# SCH_glow_cube_v2_2023-04-08_1.net
KiCad netlist of a schematic drawn in EasyEDA
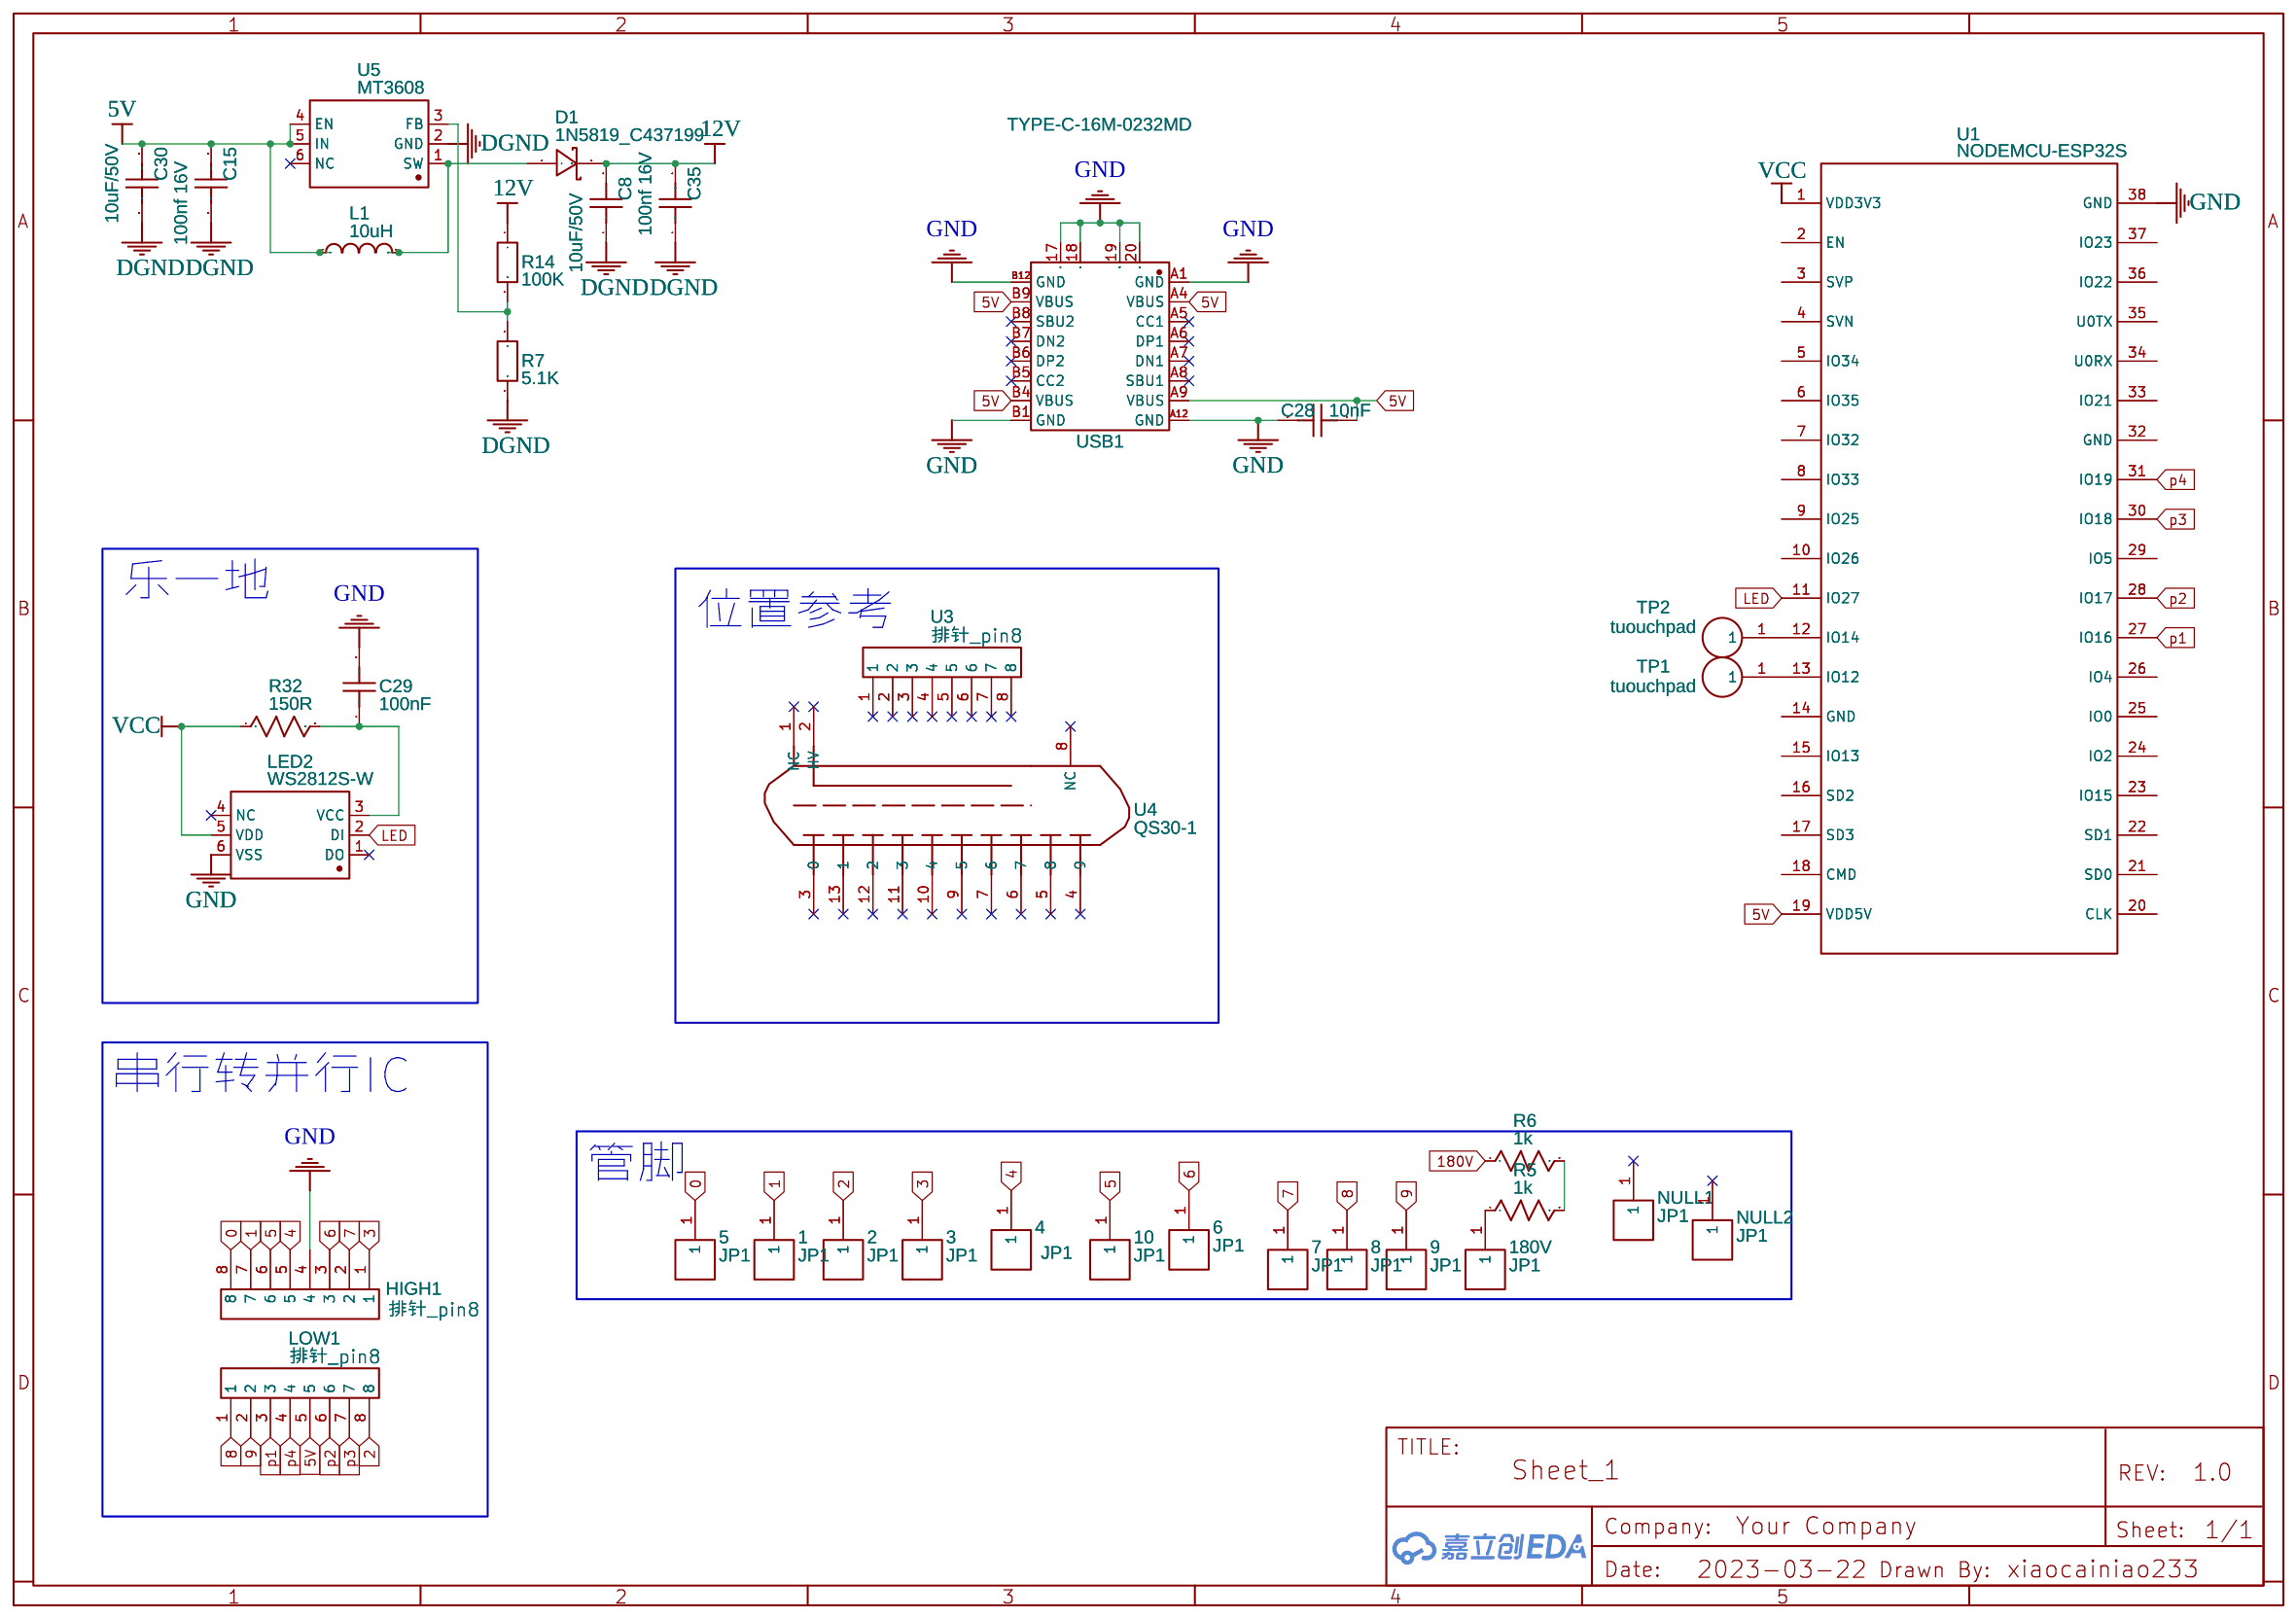
[diagram p0: schematic sheet]

(export (version "E")
  (design (tool "Eeschema 10.0.6"))
  (components
    (comp (ref "1") (value "JP1") (libsource (lib "") (part "JP1")))
    (comp (ref "2") (value "JP1") (libsource (lib "") (part "JP1")))
    (comp (ref "3") (value "JP1") (libsource (lib "") (part "JP1")))
    (comp (ref "4") (value "JP1") (libsource (lib "") (part "JP1")))
    (comp (ref "5") (value "JP1") (libsource (lib "") (part "JP1")))
    (comp (ref "6") (value "JP1") (libsource (lib "") (part "JP1")))
    (comp (ref "7") (value "JP1") (libsource (lib "") (part "JP1")))
    (comp (ref "8") (value "JP1") (libsource (lib "") (part "JP1")))
    (comp (ref "9") (value "JP1") (libsource (lib "") (part "JP1")))
    (comp (ref "10") (value "JP1") (libsource (lib "") (part "JP1")))
    (comp (ref "180V") (value "JP1") (libsource (lib "") (part "JP1_2")))
    (comp (ref "C8") (value "10uF/50V") (libsource (lib "") (part "C_0805_US")))
    (comp (ref "C15") (value "100nf 16V") (libsource (lib "") (part "C_0603_US")))
    (comp (ref "C28") (value "10nF") (libsource (lib "") (part "C_0603_US_1")))
    (comp (ref "C29") (value "100nF") (libsource (lib "") (part "C_0402_US")))
    (comp (ref "C30") (value "10uF/50V") (libsource (lib "") (part "C_0805_US")))
    (comp (ref "C35") (value "100nf 16V") (libsource (lib "") (part "C_0603_US")))
    (comp (ref "D1")
      (value "1N5819_C437199")
      (fields (field (name "BOM_Manufacturer Part") "1N5819") (field (name "BOM_Supplier Part") "C437199"))
      (libsource (lib "") (part "1N5819_C437199"))
    )
    (comp (ref "HIGH1") (value "排针_pin8") (libsource (lib "") (part "排针_pin8")))
    (comp (ref "L1")
      (value "10uH")
      (fields
        (field (name "BOM_Manufacturer Part") "ETQP3M100KVP")
        (field (name "BOM_Supplier Part") "C409619")
      )
      (libsource (lib "") (part "ETQP3M100KVP"))
    )
    (comp (ref "LED2")
      (value "WS2812S-W")
      (fields (field (name "BOM_Manufacturer Part") "WS2812S") (field (name "BOM_Supplier Part") "C114584"))
      (libsource (lib "") (part "WS2812S-W"))
    )
    (comp (ref "LOW1") (value "排针_pin8") (libsource (lib "") (part "排针_pin8_1")))
    (comp (ref "NULL1") (value "JP1") (libsource (lib "") (part "JP1_1")))
    (comp (ref "NULL2") (value "JP1") (libsource (lib "") (part "JP1_1")))
    (comp (ref "R5") (value "1k") (libsource (lib "") (part "R_AXIAL-0.3_US")))
    (comp (ref "R6") (value "1k") (libsource (lib "") (part "R_AXIAL-0.3_US")))
    (comp (ref "R7") (value "5.1K") (libsource (lib "") (part "R_0603_EU")))
    (comp (ref "R14") (value "100K") (libsource (lib "") (part "R_0603_EU")))
    (comp (ref "R32") (value "150R") (libsource (lib "") (part "R_0603_US")))
    (comp (ref "TP1") (value "tuouchpad") (libsource (lib "") (part "tuouchpad")))
    (comp (ref "TP2") (value "tuouchpad") (libsource (lib "") (part "tuouchpad")))
    (comp (ref "U1") (value "NODEMCU-ESP32S") (libsource (lib "") (part "NODEMCU-ESP32S")))
    (comp (ref "U3") (value "排针_pin8") (libsource (lib "") (part "排针_pin8_2")))
    (comp (ref "U4") (value "QS30-1") (libsource (lib "") (part "QS30-1")))
    (comp (ref "U5")
      (value "MT3608")
      (fields (field (name "BOM_Supplier Part") "C84817"))
      (libsource (lib "") (part "MT3608"))
    )
    (comp (ref "USB1")
      (value "TYPE-C-16M-0232MD")
      (fields (field (name "BOM_Supplier Part") "C2798171"))
      (libsource (lib "") (part "TYPE-C-16M-0232MD"))
    )
  )
  (nets
    (net (code "1") (name "0") (class "Default")
      (node (ref "5") (pin "1") (pinfunction "1_1") (pintype "unspecified"))
      (node (ref "HIGH1") (pin "8") (pinfunction "8_8") (pintype "unspecified"))
    )
    (net (code "2") (name "1") (class "Default")
      (node (ref "1") (pin "1") (pinfunction "1_1") (pintype "unspecified"))
      (node (ref "HIGH1") (pin "7") (pinfunction "7_7") (pintype "unspecified"))
    )
    (net (code "3") (name "2") (class "Default")
      (node (ref "2") (pin "1") (pinfunction "1_1") (pintype "unspecified"))
      (node (ref "LOW1") (pin "8") (pinfunction "8_8") (pintype "unspecified"))
    )
    (net (code "4") (name "3") (class "Default")
      (node (ref "3") (pin "1") (pinfunction "1_1") (pintype "unspecified"))
      (node (ref "HIGH1") (pin "1") (pinfunction "1_1") (pintype "unspecified"))
    )
    (net (code "5") (name "4") (class "Default")
      (node (ref "4") (pin "1") (pinfunction "1_1") (pintype "unspecified"))
      (node (ref "HIGH1") (pin "5") (pinfunction "5_5") (pintype "unspecified"))
    )
    (net (code "6") (name "5") (class "Default")
      (node (ref "10") (pin "1") (pinfunction "1_1") (pintype "unspecified"))
      (node (ref "HIGH1") (pin "6") (pinfunction "6_6") (pintype "unspecified"))
    )
    (net (code "7") (name "5V") (class "Default")
      (node (ref "C15") (pin "2") (pinfunction "2_2") (pintype "unspecified"))
      (node (ref "C28") (pin "2") (pinfunction "2_2") (pintype "unspecified"))
      (node (ref "C30") (pin "2") (pinfunction "2_2") (pintype "unspecified"))
      (node (ref "L1") (pin "1") (pinfunction "1_1") (pintype "unspecified"))
      (node (ref "LOW1") (pin "5") (pinfunction "5_5") (pintype "unspecified"))
      (node (ref "U1") (pin "19") (pinfunction "VDD5V_19") (pintype "unspecified"))
      (node (ref "U5") (pin "4") (pinfunction "EN_4") (pintype "unspecified"))
      (node (ref "U5") (pin "5") (pinfunction "IN_5") (pintype "unspecified"))
      (node (ref "USB1") (pin "A4") (pinfunction "VBUS_A4") (pintype "unspecified"))
      (node (ref "USB1") (pin "A9") (pinfunction "VBUS_A9") (pintype "unspecified"))
      (node (ref "USB1") (pin "B4") (pinfunction "VBUS_B4") (pintype "unspecified"))
      (node (ref "USB1") (pin "B9") (pinfunction "VBUS_B9") (pintype "unspecified"))
    )
    (net (code "8") (name "6") (class "Default")
      (node (ref "6") (pin "1") (pinfunction "1_1") (pintype "unspecified"))
      (node (ref "HIGH1") (pin "3") (pinfunction "3_3") (pintype "unspecified"))
    )
    (net (code "9") (name "7") (class "Default")
      (node (ref "7") (pin "1") (pinfunction "1_1") (pintype "unspecified"))
      (node (ref "HIGH1") (pin "2") (pinfunction "2_2") (pintype "unspecified"))
    )
    (net (code "10") (name "8") (class "Default")
      (node (ref "8") (pin "1") (pinfunction "1_1") (pintype "unspecified"))
      (node (ref "LOW1") (pin "1") (pinfunction "1_1") (pintype "unspecified"))
    )
    (net (code "11") (name "9") (class "Default")
      (node (ref "9") (pin "1") (pinfunction "1_1") (pintype "unspecified"))
      (node (ref "LOW1") (pin "2") (pinfunction "2_2") (pintype "unspecified"))
    )
    (net (code "12") (name "12V") (class "Default")
      (node (ref "C35") (pin "2") (pinfunction "2_2") (pintype "unspecified"))
      (node (ref "C8") (pin "2") (pinfunction "2_2") (pintype "unspecified"))
      (node (ref "D1") (pin "1") (pinfunction "C_1") (pintype "unspecified"))
      (node (ref "R14") (pin "1") (pinfunction "1_1") (pintype "unspecified"))
    )
    (net (code "13") (name "180V") (class "Default")
      (node (ref "R6") (pin "1") (pinfunction "1_1") (pintype "unspecified"))
    )
    (net (code "14") (name "DGND") (class "Default")
      (node (ref "C15") (pin "1") (pinfunction "1_1") (pintype "unspecified"))
      (node (ref "C30") (pin "1") (pinfunction "1_1") (pintype "unspecified"))
      (node (ref "C35") (pin "1") (pinfunction "1_1") (pintype "unspecified"))
      (node (ref "C8") (pin "1") (pinfunction "1_1") (pintype "unspecified"))
      (node (ref "R7") (pin "2") (pinfunction "2_2") (pintype "unspecified"))
      (node (ref "U5") (pin "2") (pinfunction "GND_2") (pintype "unspecified"))
    )
    (net (code "15") (name "GND") (class "Default")
      (node (ref "C28") (pin "1") (pinfunction "1_1") (pintype "unspecified"))
      (node (ref "C29") (pin "2") (pinfunction "2_2") (pintype "unspecified"))
      (node (ref "HIGH1") (pin "4") (pinfunction "4_4") (pintype "unspecified"))
      (node (ref "LED2") (pin "6") (pinfunction "VSS_6") (pintype "unspecified"))
      (node (ref "U1") (pin "38") (pinfunction "GND_38") (pintype "unspecified"))
      (node (ref "USB1") (pin "17") (pinfunction "17_17") (pintype "unspecified"))
      (node (ref "USB1") (pin "18") (pinfunction "18_18") (pintype "unspecified"))
      (node (ref "USB1") (pin "19") (pinfunction "19_19") (pintype "unspecified"))
      (node (ref "USB1") (pin "20") (pinfunction "20_20") (pintype "unspecified"))
      (node (ref "USB1") (pin "A1") (pinfunction "GND_A1") (pintype "unspecified"))
      (node (ref "USB1") (pin "A12") (pinfunction "GND_A12") (pintype "unspecified"))
      (node (ref "USB1") (pin "B1") (pinfunction "GND_B1") (pintype "unspecified"))
      (node (ref "USB1") (pin "B12") (pinfunction "GND_B12") (pintype "unspecified"))
    )
    (net (code "16") (name "LED") (class "Default")
      (node (ref "LED2") (pin "2") (pinfunction "DI_2") (pintype "unspecified"))
      (node (ref "U1") (pin "11") (pinfunction "IO27_11") (pintype "unspecified"))
    )
    (net (code "17") (name "Net-(180V-Pad1)") (class "Default")
      (node (ref "180V") (pin "1") (pinfunction "1_1") (pintype "unspecified"))
      (node (ref "R5") (pin "1") (pinfunction "1_1") (pintype "unspecified"))
    )
    (net (code "18") (name "Net-(D1-A)") (class "Default")
      (node (ref "D1") (pin "2") (pinfunction "A_2") (pintype "unspecified"))
      (node (ref "L1") (pin "2") (pinfunction "2_2") (pintype "unspecified"))
      (node (ref "U5") (pin "1") (pinfunction "SW_1") (pintype "unspecified"))
    )
    (net (code "19") (name "Net-(LED2-VCC)") (class "Default")
      (node (ref "C29") (pin "1") (pinfunction "1_1") (pintype "unspecified"))
      (node (ref "LED2") (pin "3") (pinfunction "VCC_3") (pintype "unspecified"))
      (node (ref "R32") (pin "2") (pinfunction "2_2") (pintype "unspecified"))
    )
    (net (code "20") (name "Net-(R5-Pad2)") (class "Default")
      (node (ref "R5") (pin "2") (pinfunction "2_2") (pintype "unspecified"))
      (node (ref "R6") (pin "2") (pinfunction "2_2") (pintype "unspecified"))
    )
    (net (code "21") (name "Net-(U1-IO12)") (class "Default")
      (node (ref "TP1") (pin "1") (pinfunction "1_1") (pintype "unspecified"))
      (node (ref "U1") (pin "13") (pinfunction "IO12_13") (pintype "unspecified"))
    )
    (net (code "22") (name "Net-(U1-IO14)") (class "Default")
      (node (ref "TP2") (pin "1") (pinfunction "1_1") (pintype "unspecified"))
      (node (ref "U1") (pin "12") (pinfunction "IO14_12") (pintype "unspecified"))
    )
    (net (code "23") (name "Net-(U5-FB)") (class "Default")
      (node (ref "R14") (pin "2") (pinfunction "2_2") (pintype "unspecified"))
      (node (ref "R7") (pin "1") (pinfunction "1_1") (pintype "unspecified"))
      (node (ref "U5") (pin "3") (pinfunction "FB_3") (pintype "unspecified"))
    )
    (net (code "24") (name "VCC") (class "Default")
      (node (ref "LED2") (pin "5") (pinfunction "VDD_5") (pintype "unspecified"))
      (node (ref "R32") (pin "1") (pinfunction "1_1") (pintype "unspecified"))
      (node (ref "U1") (pin "1") (pinfunction "VDD3V3_1") (pintype "unspecified"))
    )
    (net (code "25") (name "p1") (class "Default")
      (node (ref "LOW1") (pin "3") (pinfunction "3_3") (pintype "unspecified"))
      (node (ref "U1") (pin "27") (pinfunction "IO16_27") (pintype "unspecified"))
    )
    (net (code "26") (name "p2") (class "Default")
      (node (ref "LOW1") (pin "6") (pinfunction "6_6") (pintype "unspecified"))
      (node (ref "U1") (pin "28") (pinfunction "IO17_28") (pintype "unspecified"))
    )
    (net (code "27") (name "p3") (class "Default")
      (node (ref "LOW1") (pin "7") (pinfunction "7_7") (pintype "unspecified"))
      (node (ref "U1") (pin "30") (pinfunction "IO18_30") (pintype "unspecified"))
    )
    (net (code "28") (name "p4") (class "Default")
      (node (ref "LOW1") (pin "4") (pinfunction "4_4") (pintype "unspecified"))
      (node (ref "U1") (pin "31") (pinfunction "IO19_31") (pintype "unspecified"))
    )
    (net (code "29") (name "unconnected-(LED2-DO-Pad1)") (class "Default")
      (node (ref "LED2") (pin "1") (pinfunction "DO_1") (pintype "unspecified+no_connect"))
    )
    (net (code "30") (name "unconnected-(LED2-NC-Pad4)") (class "Default")
      (node (ref "LED2") (pin "4") (pinfunction "NC_4") (pintype "unspecified+no_connect"))
    )
    (net (code "31") (name "unconnected-(NULL1-Pad1)") (class "Default")
      (node (ref "NULL1") (pin "1") (pinfunction "1_1") (pintype "unspecified+no_connect"))
    )
    (net (code "32") (name "unconnected-(NULL2-Pad1)") (class "Default")
      (node (ref "NULL2") (pin "1") (pinfunction "1_1") (pintype "unspecified+no_connect"))
    )
    (net (code "33") (name "unconnected-(U1-CLK-Pad20)") (class "Default")
      (node (ref "U1") (pin "20") (pinfunction "CLK_20") (pintype "unspecified"))
    )
    (net (code "34") (name "unconnected-(U1-CMD-Pad18)") (class "Default")
      (node (ref "U1") (pin "18") (pinfunction "CMD_18") (pintype "unspecified"))
    )
    (net (code "35") (name "unconnected-(U1-EN-Pad2)") (class "Default")
      (node (ref "U1") (pin "2") (pinfunction "EN_2") (pintype "unspecified"))
    )
    (net (code "36") (name "unconnected-(U1-GND-Pad14)") (class "Default")
      (node (ref "U1") (pin "14") (pinfunction "GND_14") (pintype "unspecified"))
    )
    (net (code "37") (name "unconnected-(U1-GND-Pad32)") (class "Default")
      (node (ref "U1") (pin "32") (pinfunction "GND_32") (pintype "unspecified"))
    )
    (net (code "38") (name "unconnected-(U1-IO0-Pad25)") (class "Default")
      (node (ref "U1") (pin "25") (pinfunction "IO0_25") (pintype "unspecified"))
    )
    (net (code "39") (name "unconnected-(U1-IO2-Pad24)") (class "Default")
      (node (ref "U1") (pin "24") (pinfunction "IO2_24") (pintype "unspecified"))
    )
    (net (code "40") (name "unconnected-(U1-IO4-Pad26)") (class "Default")
      (node (ref "U1") (pin "26") (pinfunction "IO4_26") (pintype "unspecified"))
    )
    (net (code "41") (name "unconnected-(U1-IO5-Pad29)") (class "Default")
      (node (ref "U1") (pin "29") (pinfunction "IO5_29") (pintype "unspecified"))
    )
    (net (code "42") (name "unconnected-(U1-IO13-Pad15)") (class "Default")
      (node (ref "U1") (pin "15") (pinfunction "IO13_15") (pintype "unspecified"))
    )
    (net (code "43") (name "unconnected-(U1-IO15-Pad23)") (class "Default")
      (node (ref "U1") (pin "23") (pinfunction "IO15_23") (pintype "unspecified"))
    )
    (net (code "44") (name "unconnected-(U1-IO21-Pad33)") (class "Default")
      (node (ref "U1") (pin "33") (pinfunction "IO21_33") (pintype "unspecified"))
    )
    (net (code "45") (name "unconnected-(U1-IO22-Pad36)") (class "Default")
      (node (ref "U1") (pin "36") (pinfunction "IO22_36") (pintype "unspecified"))
    )
    (net (code "46") (name "unconnected-(U1-IO23-Pad37)") (class "Default")
      (node (ref "U1") (pin "37") (pinfunction "IO23_37") (pintype "unspecified"))
    )
    (net (code "47") (name "unconnected-(U1-IO25-Pad9)") (class "Default")
      (node (ref "U1") (pin "9") (pinfunction "IO25_9") (pintype "unspecified"))
    )
    (net (code "48") (name "unconnected-(U1-IO26-Pad10)") (class "Default")
      (node (ref "U1") (pin "10") (pinfunction "IO26_10") (pintype "unspecified"))
    )
    (net (code "49") (name "unconnected-(U1-IO32-Pad7)") (class "Default")
      (node (ref "U1") (pin "7") (pinfunction "IO32_7") (pintype "unspecified"))
    )
    (net (code "50") (name "unconnected-(U1-IO33-Pad8)") (class "Default")
      (node (ref "U1") (pin "8") (pinfunction "IO33_8") (pintype "unspecified"))
    )
    (net (code "51") (name "unconnected-(U1-IO34-Pad5)") (class "Default")
      (node (ref "U1") (pin "5") (pinfunction "IO34_5") (pintype "unspecified"))
    )
    (net (code "52") (name "unconnected-(U1-IO35-Pad6)") (class "Default")
      (node (ref "U1") (pin "6") (pinfunction "IO35_6") (pintype "unspecified"))
    )
    (net (code "53") (name "unconnected-(U1-SD0-Pad21)") (class "Default")
      (node (ref "U1") (pin "21") (pinfunction "SD0_21") (pintype "unspecified"))
    )
    (net (code "54") (name "unconnected-(U1-SD1-Pad22)") (class "Default")
      (node (ref "U1") (pin "22") (pinfunction "SD1_22") (pintype "unspecified"))
    )
    (net (code "55") (name "unconnected-(U1-SD2-Pad16)") (class "Default")
      (node (ref "U1") (pin "16") (pinfunction "SD2_16") (pintype "unspecified"))
    )
    (net (code "56") (name "unconnected-(U1-SD3-Pad17)") (class "Default")
      (node (ref "U1") (pin "17") (pinfunction "SD3_17") (pintype "unspecified"))
    )
    (net (code "57") (name "unconnected-(U1-SVN-Pad4)") (class "Default")
      (node (ref "U1") (pin "4") (pinfunction "SVN_4") (pintype "unspecified"))
    )
    (net (code "58") (name "unconnected-(U1-SVP-Pad3)") (class "Default")
      (node (ref "U1") (pin "3") (pinfunction "SVP_3") (pintype "unspecified"))
    )
    (net (code "59") (name "unconnected-(U1-U0RX-Pad34)") (class "Default")
      (node (ref "U1") (pin "34") (pinfunction "U0RX_34") (pintype "unspecified"))
    )
    (net (code "60") (name "unconnected-(U1-U0TX-Pad35)") (class "Default")
      (node (ref "U1") (pin "35") (pinfunction "U0TX_35") (pintype "unspecified"))
    )
    (net (code "61") (name "unconnected-(U3-Pad1)") (class "Default")
      (node (ref "U3") (pin "1") (pinfunction "1_1") (pintype "unspecified+no_connect"))
    )
    (net (code "62") (name "unconnected-(U3-Pad2)") (class "Default")
      (node (ref "U3") (pin "2") (pinfunction "2_2") (pintype "unspecified+no_connect"))
    )
    (net (code "63") (name "unconnected-(U3-Pad3)") (class "Default")
      (node (ref "U3") (pin "3") (pinfunction "3_3") (pintype "unspecified+no_connect"))
    )
    (net (code "64") (name "unconnected-(U3-Pad4)") (class "Default")
      (node (ref "U3") (pin "4") (pinfunction "4_4") (pintype "unspecified+no_connect"))
    )
    (net (code "65") (name "unconnected-(U3-Pad5)") (class "Default")
      (node (ref "U3") (pin "5") (pinfunction "5_5") (pintype "unspecified+no_connect"))
    )
    (net (code "66") (name "unconnected-(U3-Pad6)") (class "Default")
      (node (ref "U3") (pin "6") (pinfunction "6_6") (pintype "unspecified+no_connect"))
    )
    (net (code "67") (name "unconnected-(U3-Pad7)") (class "Default")
      (node (ref "U3") (pin "7") (pinfunction "7_7") (pintype "unspecified+no_connect"))
    )
    (net (code "68") (name "unconnected-(U3-Pad8)") (class "Default")
      (node (ref "U3") (pin "8") (pinfunction "8_8") (pintype "unspecified+no_connect"))
    )
    (net (code "69") (name "unconnected-(U4-0-Pad3)") (class "Default")
      (node (ref "U4") (pin "3") (pinfunction "0_3") (pintype "unspecified+no_connect"))
    )
    (net (code "70") (name "unconnected-(U4-1-Pad13)") (class "Default")
      (node (ref "U4") (pin "13") (pinfunction "1_13") (pintype "unspecified+no_connect"))
    )
    (net (code "71") (name "unconnected-(U4-2-Pad12)") (class "Default")
      (node (ref "U4") (pin "12") (pinfunction "2_12") (pintype "unspecified+no_connect"))
    )
    (net (code "72") (name "unconnected-(U4-3-Pad11)") (class "Default")
      (node (ref "U4") (pin "11") (pinfunction "3_11") (pintype "unspecified+no_connect"))
    )
    (net (code "73") (name "unconnected-(U4-4-Pad10)") (class "Default")
      (node (ref "U4") (pin "10") (pinfunction "4_10") (pintype "unspecified+no_connect"))
    )
    (net (code "74") (name "unconnected-(U4-5-Pad9)") (class "Default")
      (node (ref "U4") (pin "9") (pinfunction "5_9") (pintype "unspecified+no_connect"))
    )
    (net (code "75") (name "unconnected-(U4-6-Pad7)") (class "Default")
      (node (ref "U4") (pin "7") (pinfunction "6_7") (pintype "unspecified+no_connect"))
    )
    (net (code "76") (name "unconnected-(U4-7-Pad6)") (class "Default")
      (node (ref "U4") (pin "6") (pinfunction "7_6") (pintype "unspecified+no_connect"))
    )
    (net (code "77") (name "unconnected-(U4-8-Pad5)") (class "Default")
      (node (ref "U4") (pin "5") (pinfunction "8_5") (pintype "unspecified+no_connect"))
    )
    (net (code "78") (name "unconnected-(U4-9-Pad4)") (class "Default")
      (node (ref "U4") (pin "4") (pinfunction "9_4") (pintype "unspecified+no_connect"))
    )
    (net (code "79") (name "unconnected-(U4-HV-Pad2)") (class "Default")
      (node (ref "U4") (pin "2") (pinfunction "HV_2") (pintype "unspecified+no_connect"))
    )
    (net (code "80") (name "unconnected-(U4-NC-Pad1)") (class "Default")
      (node (ref "U4") (pin "1") (pinfunction "NC_1") (pintype "unspecified+no_connect"))
    )
    (net (code "81") (name "unconnected-(U4-NC-Pad8)") (class "Default")
      (node (ref "U4") (pin "8") (pinfunction "NC_8") (pintype "unspecified+no_connect"))
    )
    (net (code "82") (name "unconnected-(U5-NC-Pad6)") (class "Default")
      (node (ref "U5") (pin "6") (pinfunction "NC_6") (pintype "unspecified+no_connect"))
    )
    (net (code "83") (name "unconnected-(USB1-CC1-PadA5)") (class "Default")
      (node (ref "USB1") (pin "A5") (pinfunction "CC1_A5") (pintype "unspecified+no_connect"))
    )
    (net (code "84") (name "unconnected-(USB1-CC2-PadB5)") (class "Default")
      (node (ref "USB1") (pin "B5") (pinfunction "CC2_B5") (pintype "unspecified+no_connect"))
    )
    (net (code "85") (name "unconnected-(USB1-DN1-PadA7)") (class "Default")
      (node (ref "USB1") (pin "A7") (pinfunction "DN1_A7") (pintype "unspecified+no_connect"))
    )
    (net (code "86") (name "unconnected-(USB1-DN2-PadB7)") (class "Default")
      (node (ref "USB1") (pin "B7") (pinfunction "DN2_B7") (pintype "unspecified+no_connect"))
    )
    (net (code "87") (name "unconnected-(USB1-DP1-PadA6)") (class "Default")
      (node (ref "USB1") (pin "A6") (pinfunction "DP1_A6") (pintype "unspecified+no_connect"))
    )
    (net (code "88") (name "unconnected-(USB1-DP2-PadB6)") (class "Default")
      (node (ref "USB1") (pin "B6") (pinfunction "DP2_B6") (pintype "unspecified+no_connect"))
    )
    (net (code "89") (name "unconnected-(USB1-SBU1-PadA8)") (class "Default")
      (node (ref "USB1") (pin "A8") (pinfunction "SBU1_A8") (pintype "unspecified+no_connect"))
    )
    (net (code "90") (name "unconnected-(USB1-SBU2-PadB8)") (class "Default")
      (node (ref "USB1") (pin "B8") (pinfunction "SBU2_B8") (pintype "unspecified+no_connect"))
    )
  )
)
